# Variable_Gain_Amplifier.net
KiCad netlist of a schematic drawn in Altium Designer
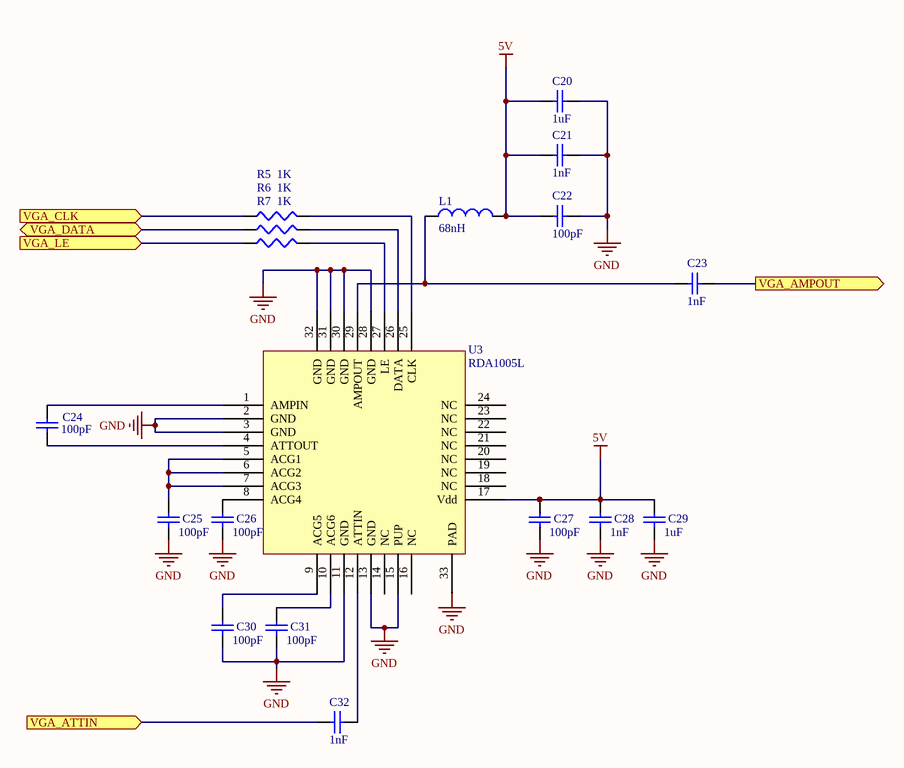
[diagram p0: Variable_Gain_Amplifier.SchDoc]

(export (version "E")
  (design (tool "Eeschema 10.0.6"))
  (components
    (comp (ref "C20")
      (value "1uF")
      (footprint "1608[0603]")
      (description "Capacitor (Semiconductor SIM Model)")
      (fields (field (name "Comment") "Cap Semi") (field (name "PUBLISHER") "Altium Limited"))
      (libsource (lib "Miscellaneous Devices") (part "Cap Semi"))
    )
    (comp (ref "C21")
      (value "1nF")
      (footprint "1608[0603]")
      (description "Capacitor (Semiconductor SIM Model)")
      (fields (field (name "Comment") "Cap Semi") (field (name "PUBLISHER") "Altium Limited"))
      (libsource (lib "Miscellaneous Devices") (part "Cap Semi"))
    )
    (comp (ref "C22")
      (value "100pF")
      (footprint "1608[0603]")
      (description "Capacitor (Semiconductor SIM Model)")
      (fields (field (name "Comment") "Cap Semi") (field (name "PUBLISHER") "Altium Limited"))
      (libsource (lib "Miscellaneous Devices") (part "Cap Semi"))
    )
    (comp (ref "C23")
      (value "1nF")
      (footprint "1608[0603]")
      (description "Capacitor (Semiconductor SIM Model)")
      (fields (field (name "Comment") "Cap Semi") (field (name "PUBLISHER") "Altium Limited"))
      (libsource (lib "Miscellaneous Devices") (part "Cap Semi"))
    )
    (comp (ref "C24")
      (value "100pF")
      (footprint "1608[0603]")
      (description "Capacitor (Semiconductor SIM Model)")
      (fields (field (name "Comment") "Cap Semi") (field (name "PUBLISHER") "Altium Limited"))
      (libsource (lib "Miscellaneous Devices") (part "Cap Semi"))
    )
    (comp (ref "C25")
      (value "100pF")
      (footprint "1608[0603]")
      (description "Capacitor (Semiconductor SIM Model)")
      (fields (field (name "Comment") "Cap Semi") (field (name "PUBLISHER") "Altium Limited"))
      (libsource (lib "Miscellaneous Devices") (part "Cap Semi"))
    )
    (comp (ref "C26")
      (value "100pF")
      (footprint "1608[0603]")
      (description "Capacitor (Semiconductor SIM Model)")
      (fields (field (name "Comment") "Cap Semi") (field (name "PUBLISHER") "Altium Limited"))
      (libsource (lib "Miscellaneous Devices") (part "Cap Semi"))
    )
    (comp (ref "C27")
      (value "100pF")
      (footprint "1608[0603]")
      (description "Capacitor (Semiconductor SIM Model)")
      (fields (field (name "Comment") "Cap Semi") (field (name "PUBLISHER") "Altium Limited"))
      (libsource (lib "Miscellaneous Devices") (part "Cap Semi"))
    )
    (comp (ref "C28")
      (value "1nF")
      (footprint "1608[0603]")
      (description "Capacitor (Semiconductor SIM Model)")
      (fields (field (name "Comment") "Cap Semi") (field (name "PUBLISHER") "Altium Limited"))
      (libsource (lib "Miscellaneous Devices") (part "Cap Semi"))
    )
    (comp (ref "C29")
      (value "1uF")
      (footprint "1608[0603]")
      (description "Capacitor (Semiconductor SIM Model)")
      (fields (field (name "Comment") "Cap Semi") (field (name "PUBLISHER") "Altium Limited"))
      (libsource (lib "Miscellaneous Devices") (part "Cap Semi"))
    )
    (comp (ref "C30")
      (value "100pF")
      (footprint "1608[0603]")
      (description "Capacitor (Semiconductor SIM Model)")
      (fields (field (name "Comment") "Cap Semi") (field (name "PUBLISHER") "Altium Limited"))
      (libsource (lib "Miscellaneous Devices") (part "Cap Semi"))
    )
    (comp (ref "C31")
      (value "100pF")
      (footprint "1608[0603]")
      (description "Capacitor (Semiconductor SIM Model)")
      (fields (field (name "Comment") "Cap Semi") (field (name "PUBLISHER") "Altium Limited"))
      (libsource (lib "Miscellaneous Devices") (part "Cap Semi"))
    )
    (comp (ref "C32")
      (value "1nF")
      (footprint "1608[0603]")
      (description "Capacitor (Semiconductor SIM Model)")
      (fields (field (name "Comment") "Cap Semi") (field (name "PUBLISHER") "Altium Limited"))
      (libsource (lib "Miscellaneous Devices") (part "Cap Semi"))
    )
    (comp (ref "L1")
      (value "68nH")
      (footprint "0603")
      (description "Inductor")
      (fields (field (name "PUBLISHER") "Altium Limited"))
      (libsource (lib "Miscellaneous Devices") (part "Inductor"))
    )
    (comp (ref "R5")
      (value "1K")
      (footprint "J1-0603")
      (description "Resistor")
      (fields (field (name "Comment") "Res3") (field (name "PUBLISHER") "Altium Limited"))
      (libsource (lib "Miscellaneous Devices") (part "Res3"))
    )
    (comp (ref "R6")
      (value "1K")
      (footprint "J1-0603")
      (description "Resistor")
      (fields (field (name "Comment") "Res3") (field (name "PUBLISHER") "Altium Limited"))
      (libsource (lib "Miscellaneous Devices") (part "Res3"))
    )
    (comp (ref "R7")
      (value "1K")
      (footprint "J1-0603")
      (description "Resistor")
      (fields (field (name "Comment") "Res3") (field (name "PUBLISHER") "Altium Limited"))
      (libsource (lib "Miscellaneous Devices") (part "Res3"))
    )
    (comp (ref "U3")
      (value "RDA1005L")
      (footprint "QFN50P500X500-32WAL")
      (description "DIGITAL CONTROLLED VARIABLE GAIN  AMPLIFIER 50 MHZ TO 4000 MHZ, 6 BIT")
      (libsource (lib "Logic_RF_Component_Symbols") (part "RDA1005L"))
    )
  )
  (nets
    (net (code "1") (name "/VGA_AMPOUT") (class "Default")
      (node (ref "C23") (pin "1") (pinfunction "1_1") (pintype "passive"))
    )
    (net (code "2") (name "/VGA_ATTIN") (class "Default")
      (node (ref "C32") (pin "2") (pinfunction "2_2") (pintype "passive"))
    )
    (net (code "3") (name "/VGA_CLK") (class "Default")
      (node (ref "R5") (pin "1") (pinfunction "1_1") (pintype "passive"))
    )
    (net (code "4") (name "/VGA_DATA") (class "Default")
      (node (ref "R6") (pin "1") (pinfunction "1_1") (pintype "passive"))
    )
    (net (code "5") (name "/VGA_LE") (class "Default")
      (node (ref "R7") (pin "1") (pinfunction "1_1") (pintype "passive"))
    )
    (net (code "6") (name "5V") (class "Default")
      (node (ref "C20") (pin "2") (pinfunction "2_2") (pintype "passive"))
      (node (ref "C21") (pin "2") (pinfunction "2_2") (pintype "passive"))
      (node (ref "C22") (pin "2") (pinfunction "2_2") (pintype "passive"))
      (node (ref "C27") (pin "2") (pinfunction "2_2") (pintype "passive"))
      (node (ref "C28") (pin "2") (pinfunction "2_2") (pintype "passive"))
      (node (ref "C29") (pin "2") (pinfunction "2_2") (pintype "passive"))
      (node (ref "L1") (pin "2") (pinfunction "2_2") (pintype "passive"))
      (node (ref "U3") (pin "17") (pinfunction "Vdd_17") (pintype "passive"))
    )
    (net (code "7") (name "GND") (class "Default")
      (node (ref "C20") (pin "1") (pinfunction "1_1") (pintype "passive"))
      (node (ref "C21") (pin "1") (pinfunction "1_1") (pintype "passive"))
      (node (ref "C22") (pin "1") (pinfunction "1_1") (pintype "passive"))
      (node (ref "C25") (pin "1") (pinfunction "1_1") (pintype "passive"))
      (node (ref "C26") (pin "1") (pinfunction "1_1") (pintype "passive"))
      (node (ref "C27") (pin "1") (pinfunction "1_1") (pintype "passive"))
      (node (ref "C28") (pin "1") (pinfunction "1_1") (pintype "passive"))
      (node (ref "C29") (pin "1") (pinfunction "1_1") (pintype "passive"))
      (node (ref "C30") (pin "1") (pinfunction "1_1") (pintype "passive"))
      (node (ref "C31") (pin "1") (pinfunction "1_1") (pintype "passive"))
      (node (ref "U3") (pin "11") (pinfunction "GND_11") (pintype "passive"))
      (node (ref "U3") (pin "13") (pinfunction "GND_13") (pintype "passive"))
      (node (ref "U3") (pin "15") (pinfunction "PUP_15") (pintype "passive"))
      (node (ref "U3") (pin "2") (pinfunction "GND_2") (pintype "passive"))
      (node (ref "U3") (pin "28") (pinfunction "GND_28") (pintype "passive"))
      (node (ref "U3") (pin "3") (pinfunction "GND_3") (pintype "passive"))
      (node (ref "U3") (pin "30") (pinfunction "GND_30") (pintype "passive"))
      (node (ref "U3") (pin "31") (pinfunction "GND_31") (pintype "passive"))
      (node (ref "U3") (pin "32") (pinfunction "GND_32") (pintype "passive"))
      (node (ref "U3") (pin "33") (pinfunction "PAD_33") (pintype "passive"))
    )
    (net (code "8") (name "Net-(U3-ACG1)") (class "Default")
      (node (ref "C25") (pin "2") (pinfunction "2_2") (pintype "passive"))
      (node (ref "U3") (pin "5") (pinfunction "ACG1_5") (pintype "passive"))
      (node (ref "U3") (pin "6") (pinfunction "ACG2_6") (pintype "passive"))
      (node (ref "U3") (pin "7") (pinfunction "ACG3_7") (pintype "passive"))
    )
    (net (code "9") (name "Net-(U3-ACG4)") (class "Default")
      (node (ref "C26") (pin "2") (pinfunction "2_2") (pintype "passive"))
      (node (ref "U3") (pin "8") (pinfunction "ACG4_8") (pintype "passive"))
    )
    (net (code "10") (name "Net-(U3-ACG5)") (class "Default")
      (node (ref "C30") (pin "2") (pinfunction "2_2") (pintype "passive"))
      (node (ref "U3") (pin "9") (pinfunction "ACG5_9") (pintype "passive"))
    )
    (net (code "11") (name "Net-(U3-ACG6)") (class "Default")
      (node (ref "C31") (pin "2") (pinfunction "2_2") (pintype "passive"))
      (node (ref "U3") (pin "10") (pinfunction "ACG6_10") (pintype "passive"))
    )
    (net (code "12") (name "Net-(U3-AMPIN)") (class "Default")
      (node (ref "C24") (pin "2") (pinfunction "2_2") (pintype "passive"))
      (node (ref "U3") (pin "1") (pinfunction "AMPIN_1") (pintype "passive"))
    )
    (net (code "13") (name "Net-(U3-AMPOUT)") (class "Default")
      (node (ref "C23") (pin "2") (pinfunction "2_2") (pintype "passive"))
      (node (ref "L1") (pin "1") (pinfunction "1_1") (pintype "passive"))
      (node (ref "U3") (pin "29") (pinfunction "AMPOUT_29") (pintype "passive"))
    )
    (net (code "14") (name "Net-(U3-ATTIN)") (class "Default")
      (node (ref "C32") (pin "1") (pinfunction "1_1") (pintype "passive"))
      (node (ref "U3") (pin "12") (pinfunction "ATTIN_12") (pintype "passive"))
    )
    (net (code "15") (name "Net-(U3-ATTOUT)") (class "Default")
      (node (ref "C24") (pin "1") (pinfunction "1_1") (pintype "passive"))
      (node (ref "U3") (pin "4") (pinfunction "ATTOUT_4") (pintype "passive"))
    )
    (net (code "16") (name "Net-(U3-CLK)") (class "Default")
      (node (ref "R5") (pin "2") (pinfunction "2_2") (pintype "passive"))
      (node (ref "U3") (pin "25") (pinfunction "CLK_25") (pintype "passive"))
    )
    (net (code "17") (name "Net-(U3-DATA)") (class "Default")
      (node (ref "R6") (pin "2") (pinfunction "2_2") (pintype "passive"))
      (node (ref "U3") (pin "26") (pinfunction "DATA_26") (pintype "passive"))
    )
    (net (code "18") (name "Net-(U3-LE)") (class "Default")
      (node (ref "R7") (pin "2") (pinfunction "2_2") (pintype "passive"))
      (node (ref "U3") (pin "27") (pinfunction "LE_27") (pintype "passive"))
    )
    (net (code "19") (name "unconnected-(U3-NC-Pad14)") (class "Default")
      (node (ref "U3") (pin "14") (pinfunction "NC_14") (pintype "passive"))
    )
    (net (code "20") (name "unconnected-(U3-NC-Pad16)") (class "Default")
      (node (ref "U3") (pin "16") (pinfunction "NC_16") (pintype "passive"))
    )
    (net (code "21") (name "unconnected-(U3-NC-Pad18)") (class "Default")
      (node (ref "U3") (pin "18") (pinfunction "NC_18") (pintype "passive"))
    )
    (net (code "22") (name "unconnected-(U3-NC-Pad19)") (class "Default")
      (node (ref "U3") (pin "19") (pinfunction "NC_19") (pintype "passive"))
    )
    (net (code "23") (name "unconnected-(U3-NC-Pad20)") (class "Default")
      (node (ref "U3") (pin "20") (pinfunction "NC_20") (pintype "passive"))
    )
    (net (code "24") (name "unconnected-(U3-NC-Pad21)") (class "Default")
      (node (ref "U3") (pin "21") (pinfunction "NC_21") (pintype "passive"))
    )
    (net (code "25") (name "unconnected-(U3-NC-Pad22)") (class "Default")
      (node (ref "U3") (pin "22") (pinfunction "NC_22") (pintype "passive"))
    )
    (net (code "26") (name "unconnected-(U3-NC-Pad23)") (class "Default")
      (node (ref "U3") (pin "23") (pinfunction "NC_23") (pintype "passive"))
    )
    (net (code "27") (name "unconnected-(U3-NC-Pad24)") (class "Default")
      (node (ref "U3") (pin "24") (pinfunction "NC_24") (pintype "passive"))
    )
  )
)
